# cv_input.net
KiCad netlist of a schematic drawn in Altium Designer
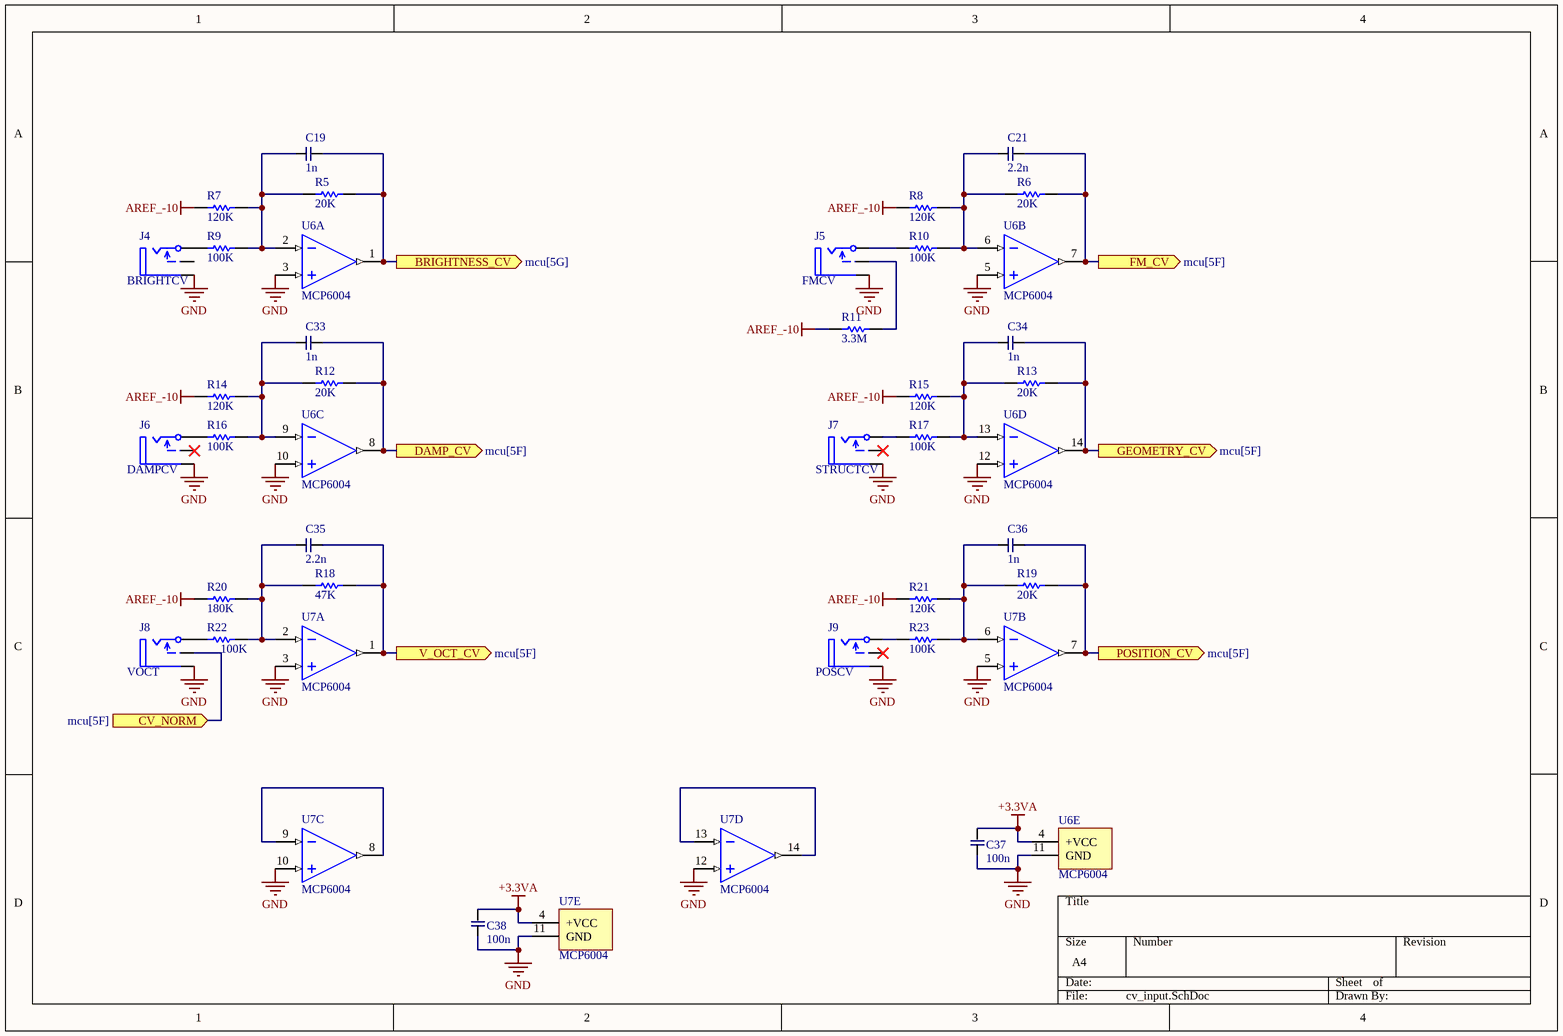
[diagram p0: cv_input.SchDoc]

(export (version "E")
  (design (tool "Eeschema 10.0.6"))
  (components
    (comp (ref "C19")
      (value "1n")
      (footprint "C0603")
      (description "Capacitor (Semiconductor SIM Model)")
      (fields (field (name "Comment") "Capacitor") (field (name "PUBLISHER") "Altium Limited"))
      (libsource (lib "ryzerd") (part "Capacitor"))
    )
    (comp (ref "C21")
      (value "2.2n")
      (footprint "C0603")
      (description "Capacitor (Semiconductor SIM Model)")
      (fields (field (name "Comment") "Capacitor") (field (name "PUBLISHER") "Altium Limited"))
      (libsource (lib "ryzerd") (part "Capacitor"))
    )
    (comp (ref "C33")
      (value "1n")
      (footprint "C0603")
      (description "Capacitor (Semiconductor SIM Model)")
      (fields (field (name "Comment") "Capacitor") (field (name "PUBLISHER") "Altium Limited"))
      (libsource (lib "ryzerd") (part "Capacitor"))
    )
    (comp (ref "C34")
      (value "1n")
      (footprint "C0603")
      (description "Capacitor (Semiconductor SIM Model)")
      (fields (field (name "Comment") "Capacitor") (field (name "PUBLISHER") "Altium Limited"))
      (libsource (lib "ryzerd") (part "Capacitor"))
    )
    (comp (ref "C35")
      (value "2.2n")
      (footprint "C0603")
      (description "Capacitor (Semiconductor SIM Model)")
      (fields (field (name "Comment") "Capacitor") (field (name "PUBLISHER") "Altium Limited"))
      (libsource (lib "ryzerd") (part "Capacitor"))
    )
    (comp (ref "C36")
      (value "1n")
      (footprint "C0603")
      (description "Capacitor (Semiconductor SIM Model)")
      (fields (field (name "Comment") "Capacitor") (field (name "PUBLISHER") "Altium Limited"))
      (libsource (lib "ryzerd") (part "Capacitor"))
    )
    (comp (ref "C37")
      (value "100n")
      (footprint "C0603")
      (description "Capacitor (Semiconductor SIM Model)")
      (fields (field (name "Comment") "Capacitor") (field (name "PUBLISHER") "Altium Limited"))
      (libsource (lib "ryzerd") (part "Capacitor"))
    )
    (comp (ref "C38")
      (value "100n")
      (footprint "C0603")
      (description "Capacitor (Semiconductor SIM Model)")
      (fields (field (name "Comment") "Capacitor") (field (name "PUBLISHER") "Altium Limited"))
      (libsource (lib "ryzerd") (part "Capacitor"))
    )
    (comp (ref "J4")
      (value "BRIGHTCV")
      (footprint "PJ301_thonk")
      (libsource (lib "ryzerd") (part "Audio_jack_mono"))
    )
    (comp (ref "J5")
      (value "FMCV")
      (footprint "PJ301_thonk")
      (libsource (lib "ryzerd") (part "Audio_jack_mono"))
    )
    (comp (ref "J6")
      (value "DAMPCV")
      (footprint "PJ301_thonk")
      (libsource (lib "ryzerd") (part "Audio_jack_mono"))
    )
    (comp (ref "J7")
      (value "STRUCTCV")
      (footprint "PJ301_thonk")
      (libsource (lib "ryzerd") (part "Audio_jack_mono"))
    )
    (comp (ref "J8")
      (value "VOCT")
      (footprint "PJ301_thonk")
      (libsource (lib "ryzerd") (part "Audio_jack_mono"))
    )
    (comp (ref "J9")
      (value "POSCV")
      (footprint "PJ301_thonk")
      (libsource (lib "ryzerd") (part "Audio_jack_mono"))
    )
    (comp (ref "R5")
      (value "20K")
      (footprint "R0603")
      (description "Resistor")
      (fields (field (name "Comment") "RESISTOR") (field (name "PUBLISHER") "Altium Limited"))
      (libsource (lib "ryzerd") (part "RESISTOR"))
    )
    (comp (ref "R6")
      (value "20K")
      (footprint "R0603")
      (description "Resistor")
      (fields (field (name "Comment") "RESISTOR") (field (name "PUBLISHER") "Altium Limited"))
      (libsource (lib "ryzerd") (part "RESISTOR"))
    )
    (comp (ref "R7")
      (value "120K")
      (footprint "R0603")
      (description "Resistor")
      (fields (field (name "Comment") "RESISTOR") (field (name "PUBLISHER") "Altium Limited"))
      (libsource (lib "ryzerd") (part "RESISTOR"))
    )
    (comp (ref "R8")
      (value "120K")
      (footprint "R0603")
      (description "Resistor")
      (fields (field (name "Comment") "RESISTOR") (field (name "PUBLISHER") "Altium Limited"))
      (libsource (lib "ryzerd") (part "RESISTOR"))
    )
    (comp (ref "R9")
      (value "100K")
      (footprint "R0603")
      (description "Resistor")
      (fields (field (name "Comment") "RESISTOR") (field (name "PUBLISHER") "Altium Limited"))
      (libsource (lib "ryzerd") (part "RESISTOR"))
    )
    (comp (ref "R10")
      (value "100K")
      (footprint "R0603")
      (description "Resistor")
      (fields (field (name "Comment") "RESISTOR") (field (name "PUBLISHER") "Altium Limited"))
      (libsource (lib "ryzerd") (part "RESISTOR"))
    )
    (comp (ref "R11")
      (value "3.3M")
      (footprint "R0603")
      (description "Resistor")
      (fields (field (name "Comment") "RESISTOR") (field (name "PUBLISHER") "Altium Limited"))
      (libsource (lib "ryzerd") (part "RESISTOR"))
    )
    (comp (ref "R12")
      (value "20K")
      (footprint "R0603")
      (description "Resistor")
      (fields (field (name "Comment") "RESISTOR") (field (name "PUBLISHER") "Altium Limited"))
      (libsource (lib "ryzerd") (part "RESISTOR"))
    )
    (comp (ref "R13")
      (value "20K")
      (footprint "R0603")
      (description "Resistor")
      (fields (field (name "Comment") "RESISTOR") (field (name "PUBLISHER") "Altium Limited"))
      (libsource (lib "ryzerd") (part "RESISTOR"))
    )
    (comp (ref "R14")
      (value "120K")
      (footprint "R0603")
      (description "Resistor")
      (fields (field (name "Comment") "RESISTOR") (field (name "PUBLISHER") "Altium Limited"))
      (libsource (lib "ryzerd") (part "RESISTOR"))
    )
    (comp (ref "R15")
      (value "120K")
      (footprint "R0603")
      (description "Resistor")
      (fields (field (name "Comment") "RESISTOR") (field (name "PUBLISHER") "Altium Limited"))
      (libsource (lib "ryzerd") (part "RESISTOR"))
    )
    (comp (ref "R16")
      (value "100K")
      (footprint "R0603")
      (description "Resistor")
      (fields (field (name "Comment") "RESISTOR") (field (name "PUBLISHER") "Altium Limited"))
      (libsource (lib "ryzerd") (part "RESISTOR"))
    )
    (comp (ref "R17")
      (value "100K")
      (footprint "R0603")
      (description "Resistor")
      (fields (field (name "Comment") "RESISTOR") (field (name "PUBLISHER") "Altium Limited"))
      (libsource (lib "ryzerd") (part "RESISTOR"))
    )
    (comp (ref "R18")
      (value "47K")
      (footprint "R0603")
      (description "Resistor")
      (fields (field (name "Comment") "RESISTOR") (field (name "PUBLISHER") "Altium Limited"))
      (libsource (lib "ryzerd") (part "RESISTOR"))
    )
    (comp (ref "R19")
      (value "20K")
      (footprint "R0603")
      (description "Resistor")
      (fields (field (name "Comment") "RESISTOR") (field (name "PUBLISHER") "Altium Limited"))
      (libsource (lib "ryzerd") (part "RESISTOR"))
    )
    (comp (ref "R20")
      (value "180K")
      (footprint "R0603")
      (description "Resistor")
      (fields (field (name "Comment") "RESISTOR") (field (name "PUBLISHER") "Altium Limited"))
      (libsource (lib "ryzerd") (part "RESISTOR"))
    )
    (comp (ref "R21")
      (value "120K")
      (footprint "R0603")
      (description "Resistor")
      (fields (field (name "Comment") "RESISTOR") (field (name "PUBLISHER") "Altium Limited"))
      (libsource (lib "ryzerd") (part "RESISTOR"))
    )
    (comp (ref "R22")
      (value "100K")
      (footprint "R0603")
      (description "Resistor")
      (fields (field (name "Comment") "RESISTOR") (field (name "PUBLISHER") "Altium Limited"))
      (libsource (lib "ryzerd") (part "RESISTOR"))
    )
    (comp (ref "R23")
      (value "100K")
      (footprint "R0603")
      (description "Resistor")
      (fields (field (name "Comment") "RESISTOR") (field (name "PUBLISHER") "Altium Limited"))
      (libsource (lib "ryzerd") (part "RESISTOR"))
    )
    (comp (ref "U6")
      (value "MCP6004")
      (footprint "SOP14_L")
      (description "Rail-to-Rail Input/Output, 10 MHz Op Amps")
      (fields (field (name "MANUFACTURER") "Texas Instruments") (field (name "PARTNUMBER") "TL074CN"))
      (libsource (lib "ryzerd") (part "MCP6004"))
    )
    (comp (ref "U7")
      (value "MCP6004")
      (footprint "SOP14_L")
      (description "Rail-to-Rail Input/Output, 10 MHz Op Amps")
      (fields (field (name "MANUFACTURER") "Texas Instruments") (field (name "PARTNUMBER") "TL074CN"))
      (libsource (lib "ryzerd") (part "MCP6004"))
    )
  )
  (nets
    (net (code "1") (name "+3.3VA") (class "Default")
      (node (ref "C37") (pin "2") (pinfunction "2_2") (pintype "passive"))
      (node (ref "C38") (pin "2") (pinfunction "2_2") (pintype "passive"))
      (node (ref "U6") (pin "4") (pinfunction "+VCC_4") (pintype "passive"))
      (node (ref "U7") (pin "4") (pinfunction "+VCC_4") (pintype "passive"))
    )
    (net (code "2") (name "/BRIGHTNESS_CV") (class "Default")
      (node (ref "C19") (pin "2") (pinfunction "2_2") (pintype "passive"))
      (node (ref "R5") (pin "2") (pinfunction "2_2") (pintype "passive"))
      (node (ref "U6") (pin "1") (pinfunction "OUT1_1") (pintype "output"))
    )
    (net (code "3") (name "/CV_NORM") (class "Default")
      (node (ref "J8") (pin "2") (pinfunction "R_Radio_ch_2") (pintype "passive"))
    )
    (net (code "4") (name "/DAMP_CV") (class "Default")
      (node (ref "C33") (pin "2") (pinfunction "2_2") (pintype "passive"))
      (node (ref "R12") (pin "2") (pinfunction "2_2") (pintype "passive"))
      (node (ref "U6") (pin "8") (pinfunction "OUT3_8") (pintype "output"))
    )
    (net (code "5") (name "/FM_CV") (class "Default")
      (node (ref "C21") (pin "2") (pinfunction "2_2") (pintype "passive"))
      (node (ref "R6") (pin "2") (pinfunction "2_2") (pintype "passive"))
      (node (ref "U6") (pin "7") (pinfunction "OUT2_7") (pintype "output"))
    )
    (net (code "6") (name "/GEOMETRY_CV") (class "Default")
      (node (ref "C34") (pin "2") (pinfunction "2_2") (pintype "passive"))
      (node (ref "R13") (pin "2") (pinfunction "2_2") (pintype "passive"))
      (node (ref "U6") (pin "14") (pinfunction "OUT4_14") (pintype "output"))
    )
    (net (code "7") (name "/POSITION_CV") (class "Default")
      (node (ref "C36") (pin "2") (pinfunction "2_2") (pintype "passive"))
      (node (ref "R19") (pin "2") (pinfunction "2_2") (pintype "passive"))
      (node (ref "U7") (pin "7") (pinfunction "OUT2_7") (pintype "output"))
    )
    (net (code "8") (name "/V_OCT_CV") (class "Default")
      (node (ref "C35") (pin "2") (pinfunction "2_2") (pintype "passive"))
      (node (ref "R18") (pin "2") (pinfunction "2_2") (pintype "passive"))
      (node (ref "U7") (pin "1") (pinfunction "OUT1_1") (pintype "output"))
    )
    (net (code "9") (name "AREF_-10") (class "Default")
      (node (ref "R11") (pin "1") (pinfunction "1_1") (pintype "passive"))
      (node (ref "R14") (pin "1") (pinfunction "1_1") (pintype "passive"))
      (node (ref "R15") (pin "1") (pinfunction "1_1") (pintype "passive"))
      (node (ref "R20") (pin "1") (pinfunction "1_1") (pintype "passive"))
      (node (ref "R21") (pin "1") (pinfunction "1_1") (pintype "passive"))
      (node (ref "R7") (pin "1") (pinfunction "1_1") (pintype "passive"))
      (node (ref "R8") (pin "1") (pinfunction "1_1") (pintype "passive"))
    )
    (net (code "10") (name "GND") (class "Default")
      (node (ref "C37") (pin "1") (pinfunction "1_1") (pintype "passive"))
      (node (ref "C38") (pin "1") (pinfunction "1_1") (pintype "passive"))
      (node (ref "J4") (pin "1") (pinfunction "Ground_1") (pintype "passive"))
      (node (ref "J5") (pin "1") (pinfunction "Ground_1") (pintype "passive"))
      (node (ref "J6") (pin "1") (pinfunction "Ground_1") (pintype "passive"))
      (node (ref "J7") (pin "1") (pinfunction "Ground_1") (pintype "passive"))
      (node (ref "J8") (pin "1") (pinfunction "Ground_1") (pintype "passive"))
      (node (ref "J9") (pin "1") (pinfunction "Ground_1") (pintype "passive"))
      (node (ref "U6") (pin "10") (pinfunction "IN3+_10") (pintype "input"))
      (node (ref "U6") (pin "11") (pinfunction "GND_11") (pintype "passive"))
      (node (ref "U6") (pin "12") (pinfunction "IN4+_12") (pintype "input"))
      (node (ref "U6") (pin "3") (pinfunction "IN1+_3") (pintype "input"))
      (node (ref "U6") (pin "5") (pinfunction "IN2+_5") (pintype "input"))
      (node (ref "U7") (pin "10") (pinfunction "IN3+_10") (pintype "input"))
      (node (ref "U7") (pin "11") (pinfunction "GND_11") (pintype "passive"))
      (node (ref "U7") (pin "12") (pinfunction "IN4+_12") (pintype "input"))
      (node (ref "U7") (pin "3") (pinfunction "IN1+_3") (pintype "input"))
      (node (ref "U7") (pin "5") (pinfunction "IN2+_5") (pintype "input"))
    )
    (net (code "11") (name "Net-(J4-R_Aux_in)") (class "Default")
      (node (ref "J4") (pin "3") (pinfunction "R_Aux_in_3") (pintype "passive"))
      (node (ref "R9") (pin "1") (pinfunction "1_1") (pintype "passive"))
    )
    (net (code "12") (name "Net-(J5-R_Aux_in)") (class "Default")
      (node (ref "J5") (pin "3") (pinfunction "R_Aux_in_3") (pintype "passive"))
      (node (ref "R10") (pin "1") (pinfunction "1_1") (pintype "passive"))
    )
    (net (code "13") (name "Net-(J5-R_Radio_ch)") (class "Default")
      (node (ref "J5") (pin "2") (pinfunction "R_Radio_ch_2") (pintype "passive"))
      (node (ref "R11") (pin "2") (pinfunction "2_2") (pintype "passive"))
    )
    (net (code "14") (name "Net-(J6-R_Aux_in)") (class "Default")
      (node (ref "J6") (pin "3") (pinfunction "R_Aux_in_3") (pintype "passive"))
      (node (ref "R16") (pin "1") (pinfunction "1_1") (pintype "passive"))
    )
    (net (code "15") (name "Net-(J7-R_Aux_in)") (class "Default")
      (node (ref "J7") (pin "3") (pinfunction "R_Aux_in_3") (pintype "passive"))
      (node (ref "R17") (pin "1") (pinfunction "1_1") (pintype "passive"))
    )
    (net (code "16") (name "Net-(J8-R_Aux_in)") (class "Default")
      (node (ref "J8") (pin "3") (pinfunction "R_Aux_in_3") (pintype "passive"))
      (node (ref "R22") (pin "1") (pinfunction "1_1") (pintype "passive"))
    )
    (net (code "17") (name "Net-(J9-R_Aux_in)") (class "Default")
      (node (ref "J9") (pin "3") (pinfunction "R_Aux_in_3") (pintype "passive"))
      (node (ref "R23") (pin "1") (pinfunction "1_1") (pintype "passive"))
    )
    (net (code "18") (name "Net-(U6A-IN1-)") (class "Default")
      (node (ref "C19") (pin "1") (pinfunction "1_1") (pintype "passive"))
      (node (ref "R5") (pin "1") (pinfunction "1_1") (pintype "passive"))
      (node (ref "R7") (pin "2") (pinfunction "2_2") (pintype "passive"))
      (node (ref "R9") (pin "2") (pinfunction "2_2") (pintype "passive"))
      (node (ref "U6") (pin "2") (pinfunction "IN1-_2") (pintype "input"))
    )
    (net (code "19") (name "Net-(U6B-IN2-)") (class "Default")
      (node (ref "C21") (pin "1") (pinfunction "1_1") (pintype "passive"))
      (node (ref "R10") (pin "2") (pinfunction "2_2") (pintype "passive"))
      (node (ref "R6") (pin "1") (pinfunction "1_1") (pintype "passive"))
      (node (ref "R8") (pin "2") (pinfunction "2_2") (pintype "passive"))
      (node (ref "U6") (pin "6") (pinfunction "IN2-_6") (pintype "input"))
    )
    (net (code "20") (name "Net-(U6C-IN3-)") (class "Default")
      (node (ref "C33") (pin "1") (pinfunction "1_1") (pintype "passive"))
      (node (ref "R12") (pin "1") (pinfunction "1_1") (pintype "passive"))
      (node (ref "R14") (pin "2") (pinfunction "2_2") (pintype "passive"))
      (node (ref "R16") (pin "2") (pinfunction "2_2") (pintype "passive"))
      (node (ref "U6") (pin "9") (pinfunction "IN3-_9") (pintype "input"))
    )
    (net (code "21") (name "Net-(U6D-IN4-)") (class "Default")
      (node (ref "C34") (pin "1") (pinfunction "1_1") (pintype "passive"))
      (node (ref "R13") (pin "1") (pinfunction "1_1") (pintype "passive"))
      (node (ref "R15") (pin "2") (pinfunction "2_2") (pintype "passive"))
      (node (ref "R17") (pin "2") (pinfunction "2_2") (pintype "passive"))
      (node (ref "U6") (pin "13") (pinfunction "IN4-_13") (pintype "input"))
    )
    (net (code "22") (name "Net-(U7A-IN1-)") (class "Default")
      (node (ref "C35") (pin "1") (pinfunction "1_1") (pintype "passive"))
      (node (ref "R18") (pin "1") (pinfunction "1_1") (pintype "passive"))
      (node (ref "R20") (pin "2") (pinfunction "2_2") (pintype "passive"))
      (node (ref "R22") (pin "2") (pinfunction "2_2") (pintype "passive"))
      (node (ref "U7") (pin "2") (pinfunction "IN1-_2") (pintype "input"))
    )
    (net (code "23") (name "Net-(U7B-IN2-)") (class "Default")
      (node (ref "C36") (pin "1") (pinfunction "1_1") (pintype "passive"))
      (node (ref "R19") (pin "1") (pinfunction "1_1") (pintype "passive"))
      (node (ref "R21") (pin "2") (pinfunction "2_2") (pintype "passive"))
      (node (ref "R23") (pin "2") (pinfunction "2_2") (pintype "passive"))
      (node (ref "U7") (pin "6") (pinfunction "IN2-_6") (pintype "input"))
    )
    (net (code "24") (name "Net-(U7C-IN3-)") (class "Default")
      (node (ref "U7") (pin "8") (pinfunction "OUT3_8") (pintype "output"))
      (node (ref "U7") (pin "9") (pinfunction "IN3-_9") (pintype "input"))
    )
    (net (code "25") (name "Net-(U7D-IN4-)") (class "Default")
      (node (ref "U7") (pin "13") (pinfunction "IN4-_13") (pintype "input"))
      (node (ref "U7") (pin "14") (pinfunction "OUT4_14") (pintype "output"))
    )
    (net (code "26") (name "unconnected-(J4-R_Radio_ch-Pad2)") (class "Default")
      (node (ref "J4") (pin "2") (pinfunction "R_Radio_ch_2") (pintype "passive"))
    )
    (net (code "27") (name "unconnected-(J6-R_Radio_ch-Pad2)") (class "Default")
      (node (ref "J6") (pin "2") (pinfunction "R_Radio_ch_2") (pintype "passive+no_connect"))
    )
    (net (code "28") (name "unconnected-(J7-R_Radio_ch-Pad2)") (class "Default")
      (node (ref "J7") (pin "2") (pinfunction "R_Radio_ch_2") (pintype "passive+no_connect"))
    )
    (net (code "29") (name "unconnected-(J9-R_Radio_ch-Pad2)") (class "Default")
      (node (ref "J9") (pin "2") (pinfunction "R_Radio_ch_2") (pintype "passive+no_connect"))
    )
  )
)
